# BLOCK6.net
KiCad netlist of a schematic drawn in Altium Designer
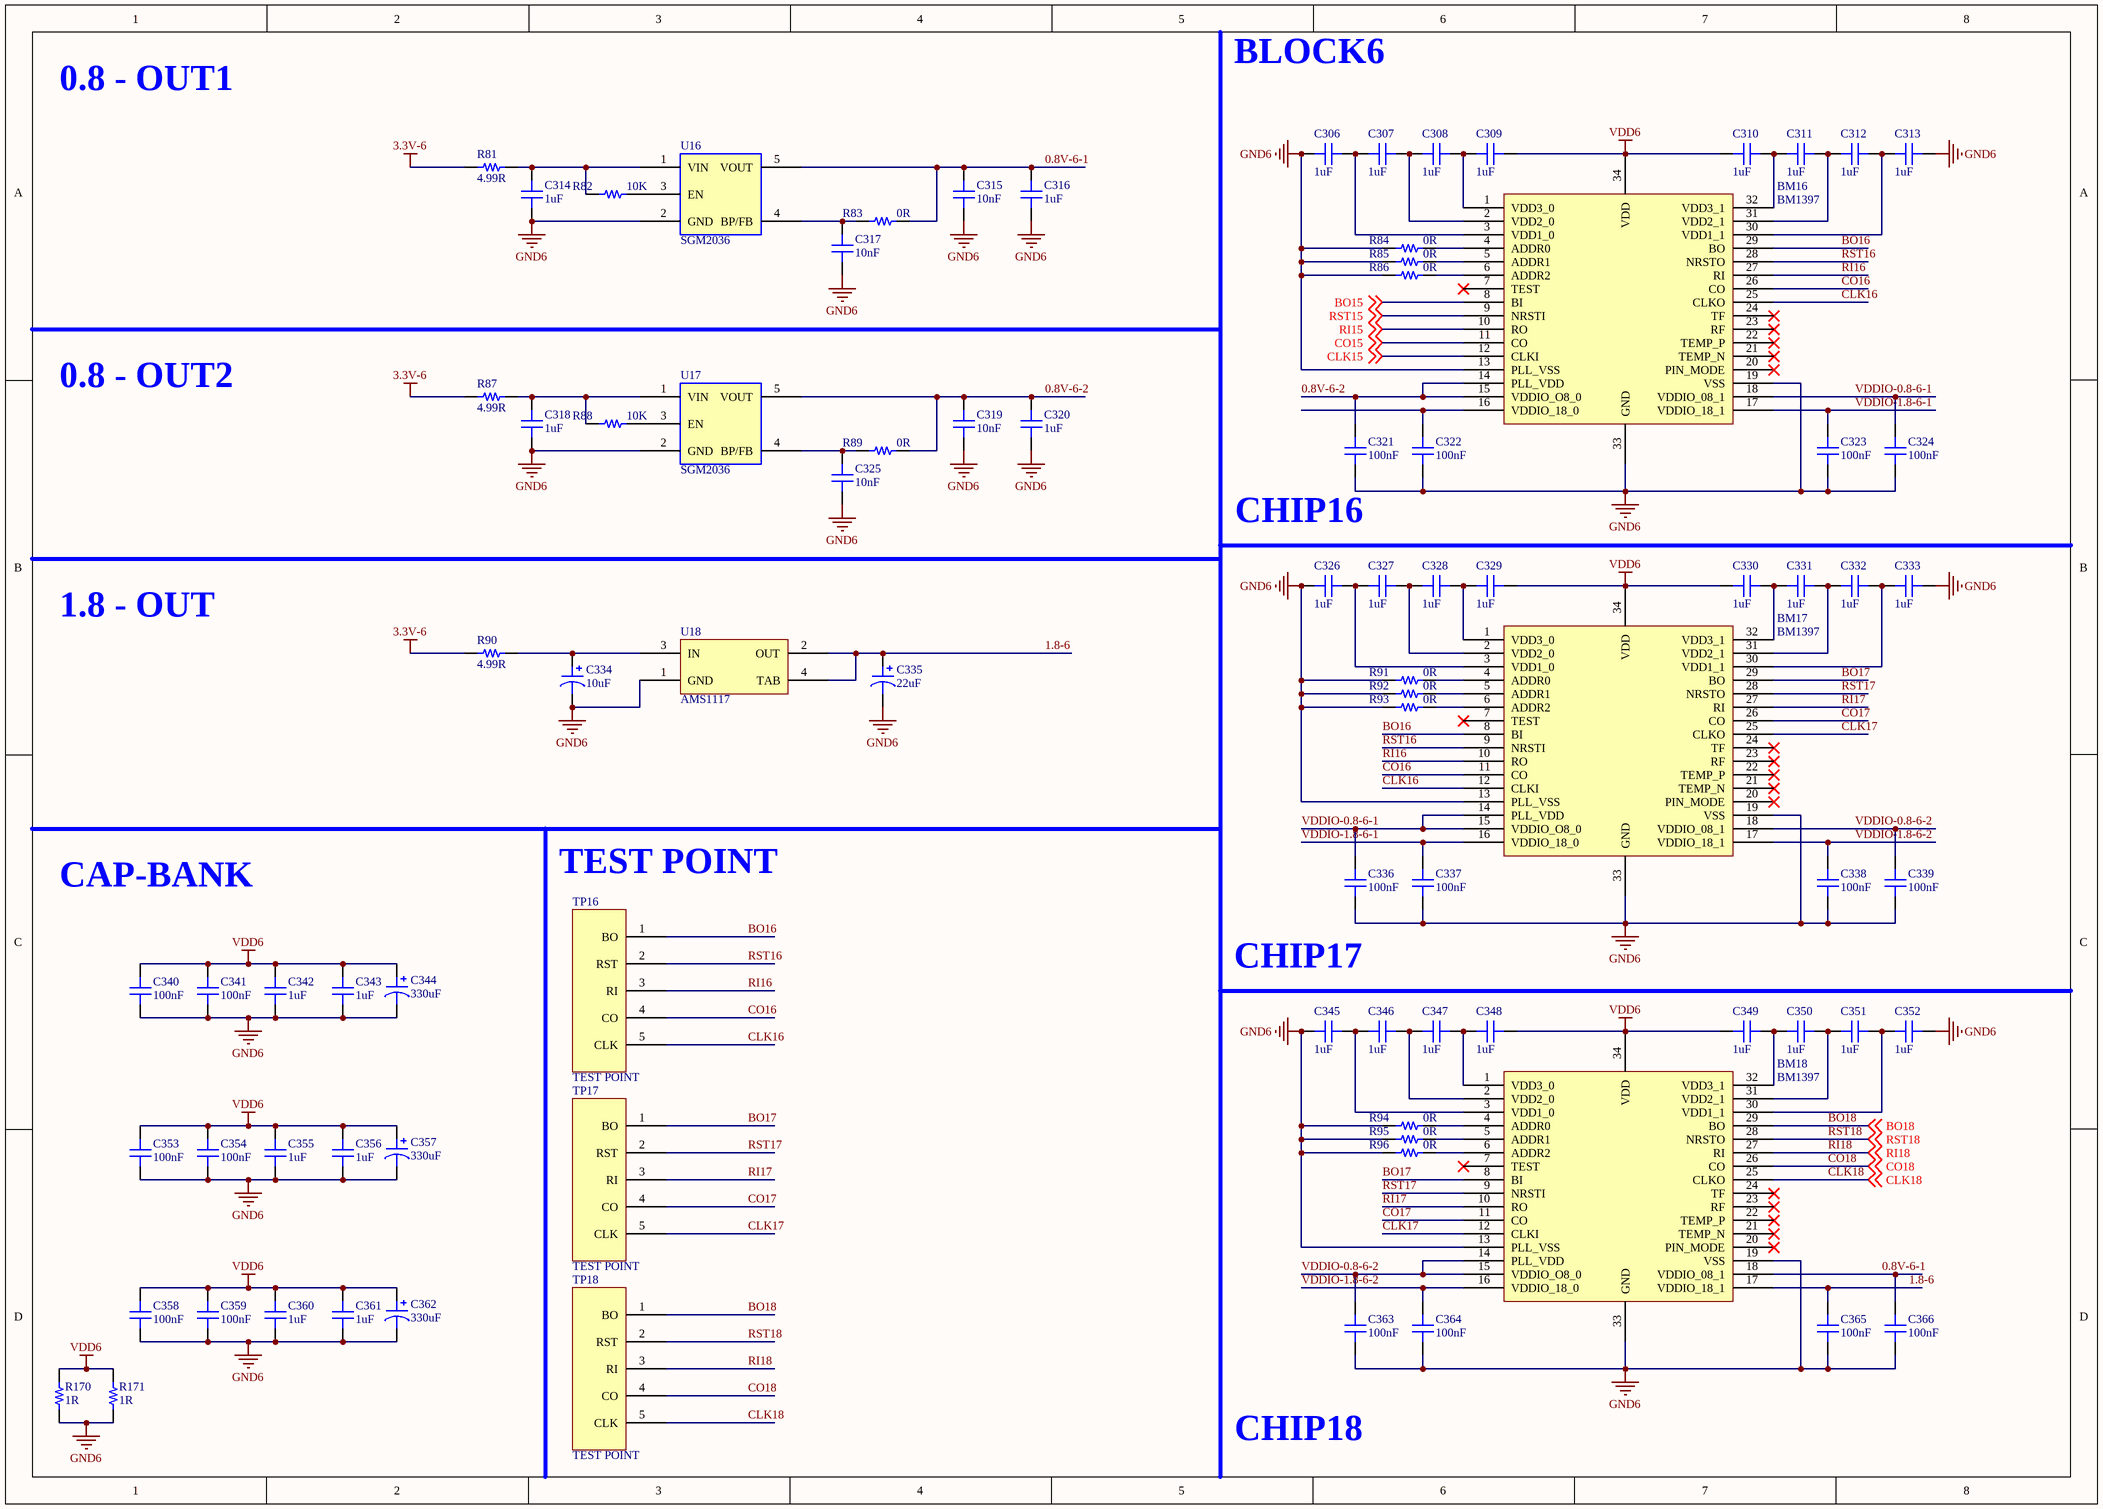
[diagram p0: BLOCK6.SchDoc]

(export (version "E")
  (design (tool "Eeschema 10.0.6"))
  (components
    (comp (ref "BM16") (value "BM1397") (footprint "BM1387") (libsource (lib "Miner_8TH") (part "BM1397_1")))
    (comp (ref "BM17") (value "BM1397") (footprint "BM1387") (libsource (lib "Miner_8TH") (part "BM1397_1")))
    (comp (ref "BM18") (value "BM1397") (footprint "BM1387") (libsource (lib "Miner_8TH") (part "BM1397_1")))
    (comp (ref "C306") (value "1uF") (footprint "CAP-SMD-0603") (libsource (lib "Miner_8TH") (part "CAP")))
    (comp (ref "C307") (value "1uF") (footprint "CAP-SMD-0603") (libsource (lib "Miner_8TH") (part "CAP")))
    (comp (ref "C308") (value "1uF") (footprint "CAP-SMD-0603") (libsource (lib "Miner_8TH") (part "CAP")))
    (comp (ref "C309") (value "1uF") (footprint "CAP-SMD-0603") (libsource (lib "Miner_8TH") (part "CAP")))
    (comp (ref "C310") (value "1uF") (footprint "CAP-SMD-0603") (libsource (lib "Miner_8TH") (part "CAP")))
    (comp (ref "C311") (value "1uF") (footprint "CAP-SMD-0603") (libsource (lib "Miner_8TH") (part "CAP")))
    (comp (ref "C312") (value "1uF") (footprint "CAP-SMD-0603") (libsource (lib "Miner_8TH") (part "CAP")))
    (comp (ref "C313") (value "1uF") (footprint "CAP-SMD-0603") (libsource (lib "Miner_8TH") (part "CAP")))
    (comp (ref "C314") (value "1uF") (footprint "CAP_SMD_0805") (libsource (lib "Miner_8TH") (part "CAP")))
    (comp (ref "C315") (value "10nF") (footprint "CAP_SMD_0805") (libsource (lib "Miner_8TH") (part "CAP")))
    (comp (ref "C316") (value "1uF") (footprint "CAP_SMD_0805") (libsource (lib "Miner_8TH") (part "CAP")))
    (comp (ref "C317") (value "10nF") (footprint "CAP_SMD_0805") (libsource (lib "Miner_8TH") (part "CAP")))
    (comp (ref "C318") (value "1uF") (footprint "CAP_SMD_0805") (libsource (lib "Miner_8TH") (part "CAP")))
    (comp (ref "C319") (value "10nF") (footprint "CAP_SMD_0805") (libsource (lib "Miner_8TH") (part "CAP")))
    (comp (ref "C320") (value "1uF") (footprint "CAP_SMD_0805") (libsource (lib "Miner_8TH") (part "CAP")))
    (comp (ref "C321") (value "100nF") (footprint "CAP_SMD_0805") (libsource (lib "Miner_8TH") (part "CAP")))
    (comp (ref "C322") (value "100nF") (footprint "CAP_SMD_0805") (libsource (lib "Miner_8TH") (part "CAP")))
    (comp (ref "C323") (value "100nF") (footprint "CAP_SMD_0805") (libsource (lib "Miner_8TH") (part "CAP")))
    (comp (ref "C324") (value "100nF") (footprint "CAP_SMD_0805") (libsource (lib "Miner_8TH") (part "CAP")))
    (comp (ref "C325") (value "10nF") (footprint "CAP_SMD_0805") (libsource (lib "Miner_8TH") (part "CAP")))
    (comp (ref "C326") (value "1uF") (footprint "CAP-SMD-0603") (libsource (lib "Miner_8TH") (part "CAP")))
    (comp (ref "C327") (value "1uF") (footprint "CAP-SMD-0603") (libsource (lib "Miner_8TH") (part "CAP")))
    (comp (ref "C328") (value "1uF") (footprint "CAP-SMD-0603") (libsource (lib "Miner_8TH") (part "CAP")))
    (comp (ref "C329") (value "1uF") (footprint "CAP-SMD-0603") (libsource (lib "Miner_8TH") (part "CAP")))
    (comp (ref "C330") (value "1uF") (footprint "CAP-SMD-0603") (libsource (lib "Miner_8TH") (part "CAP")))
    (comp (ref "C331") (value "1uF") (footprint "CAP-SMD-0603") (libsource (lib "Miner_8TH") (part "CAP")))
    (comp (ref "C332") (value "1uF") (footprint "CAP-SMD-0603") (libsource (lib "Miner_8TH") (part "CAP")))
    (comp (ref "C333") (value "1uF") (footprint "CAP-SMD-0603") (libsource (lib "Miner_8TH") (part "CAP")))
    (comp (ref "C334")
      (value "10uF")
      (footprint "CAP-TAN-CASE-A")
      (libsource (lib "Miner_8TH") (part "POLARIZED CAP"))
    )
    (comp (ref "C335")
      (value "22uF")
      (footprint "CAP-TAN-CASE-A")
      (libsource (lib "Miner_8TH") (part "POLARIZED CAP"))
    )
    (comp (ref "C336") (value "100nF") (footprint "CAP_SMD_0805") (libsource (lib "Miner_8TH") (part "CAP")))
    (comp (ref "C337") (value "100nF") (footprint "CAP_SMD_0805") (libsource (lib "Miner_8TH") (part "CAP")))
    (comp (ref "C338") (value "100nF") (footprint "CAP_SMD_0805") (libsource (lib "Miner_8TH") (part "CAP")))
    (comp (ref "C339") (value "100nF") (footprint "CAP_SMD_0805") (libsource (lib "Miner_8TH") (part "CAP")))
    (comp (ref "C340") (value "100nF") (footprint "CAP_SMD_0805") (libsource (lib "Miner_8TH") (part "CAP")))
    (comp (ref "C341") (value "100nF") (footprint "CAP_SMD_0805") (libsource (lib "Miner_8TH") (part "CAP")))
    (comp (ref "C342") (value "1uF") (footprint "CAP_SMD_0805") (libsource (lib "Miner_8TH") (part "CAP")))
    (comp (ref "C343") (value "1uF") (footprint "CAP_SMD_0805") (libsource (lib "Miner_8TH") (part "CAP")))
    (comp (ref "C344")
      (value "330uF")
      (footprint "CAP-TAN-CASE-E")
      (libsource (lib "Miner_8TH") (part "POLARIZED CAP"))
    )
    (comp (ref "C345") (value "1uF") (footprint "CAP-SMD-0603") (libsource (lib "Miner_8TH") (part "CAP")))
    (comp (ref "C346") (value "1uF") (footprint "CAP-SMD-0603") (libsource (lib "Miner_8TH") (part "CAP")))
    (comp (ref "C347") (value "1uF") (footprint "CAP-SMD-0603") (libsource (lib "Miner_8TH") (part "CAP")))
    (comp (ref "C348") (value "1uF") (footprint "CAP-SMD-0603") (libsource (lib "Miner_8TH") (part "CAP")))
    (comp (ref "C349") (value "1uF") (footprint "CAP-SMD-0603") (libsource (lib "Miner_8TH") (part "CAP")))
    (comp (ref "C350") (value "1uF") (footprint "CAP-SMD-0603") (libsource (lib "Miner_8TH") (part "CAP")))
    (comp (ref "C351") (value "1uF") (footprint "CAP-SMD-0603") (libsource (lib "Miner_8TH") (part "CAP")))
    (comp (ref "C352") (value "1uF") (footprint "CAP-SMD-0603") (libsource (lib "Miner_8TH") (part "CAP")))
    (comp (ref "C353") (value "100nF") (footprint "CAP_SMD_0805") (libsource (lib "Miner_8TH") (part "CAP")))
    (comp (ref "C354") (value "100nF") (footprint "CAP_SMD_0805") (libsource (lib "Miner_8TH") (part "CAP")))
    (comp (ref "C355") (value "1uF") (footprint "CAP_SMD_0805") (libsource (lib "Miner_8TH") (part "CAP")))
    (comp (ref "C356") (value "1uF") (footprint "CAP_SMD_0805") (libsource (lib "Miner_8TH") (part "CAP")))
    (comp (ref "C357")
      (value "330uF")
      (footprint "CAP-TAN-CASE-E")
      (libsource (lib "Miner_8TH") (part "POLARIZED CAP"))
    )
    (comp (ref "C358") (value "100nF") (footprint "CAP_SMD_0805") (libsource (lib "Miner_8TH") (part "CAP")))
    (comp (ref "C359") (value "100nF") (footprint "CAP_SMD_0805") (libsource (lib "Miner_8TH") (part "CAP")))
    (comp (ref "C360") (value "1uF") (footprint "CAP_SMD_0805") (libsource (lib "Miner_8TH") (part "CAP")))
    (comp (ref "C361") (value "1uF") (footprint "CAP_SMD_0805") (libsource (lib "Miner_8TH") (part "CAP")))
    (comp (ref "C362")
      (value "330uF")
      (footprint "CAP-TAN-CASE-E")
      (libsource (lib "Miner_8TH") (part "POLARIZED CAP"))
    )
    (comp (ref "C363") (value "100nF") (footprint "CAP_SMD_0805") (libsource (lib "Miner_8TH") (part "CAP")))
    (comp (ref "C364") (value "100nF") (footprint "CAP_SMD_0805") (libsource (lib "Miner_8TH") (part "CAP")))
    (comp (ref "C365") (value "100nF") (footprint "CAP_SMD_0805") (libsource (lib "Miner_8TH") (part "CAP")))
    (comp (ref "C366") (value "100nF") (footprint "CAP_SMD_0805") (libsource (lib "Miner_8TH") (part "CAP")))
    (comp (ref "R81") (value "4.99R") (footprint "RES-SMD-1206") (libsource (lib "Miner_8TH") (part "RES")))
    (comp (ref "R82") (value "10K") (footprint "RES-SMD-0402") (libsource (lib "Miner_8TH") (part "RES")))
    (comp (ref "R83") (value "0R") (footprint "RES-SMD-0402") (libsource (lib "Miner_8TH") (part "RES")))
    (comp (ref "R84") (value "0R") (footprint "RES-SMD-0402") (libsource (lib "Miner_8TH") (part "RES")))
    (comp (ref "R85") (value "0R") (footprint "RES-SMD-0402") (libsource (lib "Miner_8TH") (part "RES")))
    (comp (ref "R86") (value "0R") (footprint "RES-SMD-0402") (libsource (lib "Miner_8TH") (part "RES")))
    (comp (ref "R87") (value "4.99R") (footprint "RES-SMD-1206") (libsource (lib "Miner_8TH") (part "RES")))
    (comp (ref "R88") (value "10K") (footprint "RES-SMD-0402") (libsource (lib "Miner_8TH") (part "RES")))
    (comp (ref "R89") (value "0R") (footprint "RES-SMD-0402") (libsource (lib "Miner_8TH") (part "RES")))
    (comp (ref "R90") (value "4.99R") (footprint "RES-SMD-1206") (libsource (lib "Miner_8TH") (part "RES")))
    (comp (ref "R91") (value "0R") (footprint "RES-SMD-0402") (libsource (lib "Miner_8TH") (part "RES")))
    (comp (ref "R92") (value "0R") (footprint "RES-SMD-0402") (libsource (lib "Miner_8TH") (part "RES")))
    (comp (ref "R93") (value "0R") (footprint "RES-SMD-0402") (libsource (lib "Miner_8TH") (part "RES")))
    (comp (ref "R94") (value "0R") (footprint "RES-SMD-0402") (libsource (lib "Miner_8TH") (part "RES")))
    (comp (ref "R95") (value "0R") (footprint "RES-SMD-0402") (libsource (lib "Miner_8TH") (part "RES")))
    (comp (ref "R96") (value "0R") (footprint "RES-SMD-0402") (libsource (lib "Miner_8TH") (part "RES")))
    (comp (ref "R170") (value "1R") (footprint "RES-SMD-1210") (libsource (lib "Miner_8TH") (part "RES")))
    (comp (ref "R171") (value "1R") (footprint "RES-SMD-1210") (libsource (lib "Miner_8TH") (part "RES")))
    (comp (ref "TP16")
      (value "TEST POINT")
      (footprint "TEST_POINT")
      (libsource (lib "Miner_8TH") (part "TEST POINT"))
    )
    (comp (ref "TP17")
      (value "TEST POINT")
      (footprint "TEST_POINT")
      (libsource (lib "Miner_8TH") (part "TEST POINT"))
    )
    (comp (ref "TP18")
      (value "TEST POINT")
      (footprint "TEST_POINT")
      (libsource (lib "Miner_8TH") (part "TEST POINT"))
    )
    (comp (ref "U16")
      (value "SGM2036")
      (footprint "SOT23-5PIN")
      (libsource (lib "Miner_8TH") (part "SGM2036"))
    )
    (comp (ref "U17")
      (value "SGM2036")
      (footprint "SOT23-5PIN")
      (libsource (lib "Miner_8TH") (part "SGM2036"))
    )
    (comp (ref "U18") (value "AMS1117") (footprint "AMS1117") (libsource (lib "Miner_8TH") (part "AMS1117")))
  )
  (nets
    (net (code "1") (name "/0.8V-6-1") (class "Default")
      (node (ref "BM18") (pin "18") (pinfunction "VDDIO_08_1_18") (pintype "passive"))
      (node (ref "C315") (pin "2") (pinfunction "2_2") (pintype "passive"))
      (node (ref "C316") (pin "2") (pinfunction "2_2") (pintype "passive"))
      (node (ref "C366") (pin "2") (pinfunction "2_2") (pintype "passive"))
      (node (ref "R83") (pin "2") (pinfunction "2_2") (pintype "passive"))
      (node (ref "U16") (pin "5") (pinfunction "VOUT_5") (pintype "passive"))
    )
    (net (code "2") (name "/0.8V-6-2") (class "Default")
      (node (ref "BM16") (pin "14") (pinfunction "PLL_VDD_14") (pintype "passive"))
      (node (ref "BM16") (pin "15") (pinfunction "VDDIO_O8_0_15") (pintype "passive"))
      (node (ref "C319") (pin "2") (pinfunction "2_2") (pintype "passive"))
      (node (ref "C320") (pin "2") (pinfunction "2_2") (pintype "passive"))
      (node (ref "C321") (pin "2") (pinfunction "2_2") (pintype "passive"))
      (node (ref "R89") (pin "2") (pinfunction "2_2") (pintype "passive"))
      (node (ref "U17") (pin "5") (pinfunction "VOUT_5") (pintype "passive"))
    )
    (net (code "3") (name "/1.8-6") (class "Default")
      (node (ref "BM18") (pin "17") (pinfunction "VDDIO_18_1_17") (pintype "passive"))
      (node (ref "C335") (pin "1") (pinfunction "1_1") (pintype "passive"))
      (node (ref "C365") (pin "2") (pinfunction "2_2") (pintype "passive"))
      (node (ref "U18") (pin "2") (pinfunction "OUT_2") (pintype "passive"))
      (node (ref "U18") (pin "4") (pinfunction "TAB_4") (pintype "passive"))
    )
    (net (code "4") (name "/BO16") (class "Default")
      (node (ref "BM16") (pin "29") (pinfunction "BO_29") (pintype "passive"))
      (node (ref "BM17") (pin "8") (pinfunction "BI_8") (pintype "passive"))
      (node (ref "TP16") (pin "1") (pinfunction "BO_1") (pintype "passive"))
    )
    (net (code "5") (name "/BO17") (class "Default")
      (node (ref "BM17") (pin "29") (pinfunction "BO_29") (pintype "passive"))
      (node (ref "BM18") (pin "8") (pinfunction "BI_8") (pintype "passive"))
      (node (ref "TP17") (pin "1") (pinfunction "BO_1") (pintype "passive"))
    )
    (net (code "6") (name "/CLK16") (class "Default")
      (node (ref "BM16") (pin "25") (pinfunction "CLKO_25") (pintype "passive"))
      (node (ref "BM17") (pin "12") (pinfunction "CLKI_12") (pintype "passive"))
      (node (ref "TP16") (pin "5") (pinfunction "CLK_5") (pintype "passive"))
    )
    (net (code "7") (name "/CLK17") (class "Default")
      (node (ref "BM17") (pin "25") (pinfunction "CLKO_25") (pintype "passive"))
      (node (ref "BM18") (pin "12") (pinfunction "CLKI_12") (pintype "passive"))
      (node (ref "TP17") (pin "5") (pinfunction "CLK_5") (pintype "passive"))
    )
    (net (code "8") (name "/CO16") (class "Default")
      (node (ref "BM16") (pin "26") (pinfunction "CO_26") (pintype "passive"))
      (node (ref "BM17") (pin "11") (pinfunction "CO_11") (pintype "passive"))
      (node (ref "TP16") (pin "4") (pinfunction "CO_4") (pintype "passive"))
    )
    (net (code "9") (name "/CO17") (class "Default")
      (node (ref "BM17") (pin "26") (pinfunction "CO_26") (pintype "passive"))
      (node (ref "BM18") (pin "11") (pinfunction "CO_11") (pintype "passive"))
      (node (ref "TP17") (pin "4") (pinfunction "CO_4") (pintype "passive"))
    )
    (net (code "10") (name "/RI16") (class "Default")
      (node (ref "BM16") (pin "27") (pinfunction "RI_27") (pintype "passive"))
      (node (ref "BM17") (pin "10") (pinfunction "RO_10") (pintype "passive"))
      (node (ref "TP16") (pin "3") (pinfunction "RI_3") (pintype "passive"))
    )
    (net (code "11") (name "/RI17") (class "Default")
      (node (ref "BM17") (pin "27") (pinfunction "RI_27") (pintype "passive"))
      (node (ref "BM18") (pin "10") (pinfunction "RO_10") (pintype "passive"))
      (node (ref "TP17") (pin "3") (pinfunction "RI_3") (pintype "passive"))
    )
    (net (code "12") (name "/RST16") (class "Default")
      (node (ref "BM16") (pin "28") (pinfunction "NRSTO_28") (pintype "passive"))
      (node (ref "BM17") (pin "9") (pinfunction "NRSTI_9") (pintype "passive"))
      (node (ref "TP16") (pin "2") (pinfunction "RST_2") (pintype "passive"))
    )
    (net (code "13") (name "/RST17") (class "Default")
      (node (ref "BM17") (pin "28") (pinfunction "NRSTO_28") (pintype "passive"))
      (node (ref "BM18") (pin "9") (pinfunction "NRSTI_9") (pintype "passive"))
      (node (ref "TP17") (pin "2") (pinfunction "RST_2") (pintype "passive"))
    )
    (net (code "14") (name "/VDDIO-0.8-6-1") (class "Default")
      (node (ref "BM16") (pin "18") (pinfunction "VDDIO_08_1_18") (pintype "passive"))
      (node (ref "BM17") (pin "14") (pinfunction "PLL_VDD_14") (pintype "passive"))
      (node (ref "BM17") (pin "15") (pinfunction "VDDIO_O8_0_15") (pintype "passive"))
      (node (ref "C324") (pin "2") (pinfunction "2_2") (pintype "passive"))
      (node (ref "C336") (pin "2") (pinfunction "2_2") (pintype "passive"))
    )
    (net (code "15") (name "/VDDIO-0.8-6-2") (class "Default")
      (node (ref "BM17") (pin "18") (pinfunction "VDDIO_08_1_18") (pintype "passive"))
      (node (ref "BM18") (pin "14") (pinfunction "PLL_VDD_14") (pintype "passive"))
      (node (ref "BM18") (pin "15") (pinfunction "VDDIO_O8_0_15") (pintype "passive"))
      (node (ref "C339") (pin "2") (pinfunction "2_2") (pintype "passive"))
      (node (ref "C363") (pin "2") (pinfunction "2_2") (pintype "passive"))
    )
    (net (code "16") (name "/VDDIO-1.8-6-1") (class "Default")
      (node (ref "BM16") (pin "17") (pinfunction "VDDIO_18_1_17") (pintype "passive"))
      (node (ref "BM17") (pin "16") (pinfunction "VDDIO_18_0_16") (pintype "passive"))
      (node (ref "C323") (pin "2") (pinfunction "2_2") (pintype "passive"))
      (node (ref "C337") (pin "2") (pinfunction "2_2") (pintype "passive"))
    )
    (net (code "17") (name "/VDDIO-1.8-6-2") (class "Default")
      (node (ref "BM17") (pin "17") (pinfunction "VDDIO_18_1_17") (pintype "passive"))
      (node (ref "BM18") (pin "16") (pinfunction "VDDIO_18_0_16") (pintype "passive"))
      (node (ref "C338") (pin "2") (pinfunction "2_2") (pintype "passive"))
      (node (ref "C364") (pin "2") (pinfunction "2_2") (pintype "passive"))
    )
    (net (code "18") (name "3.3V-6") (class "Default")
      (node (ref "R81") (pin "1") (pinfunction "1_1") (pintype "passive"))
      (node (ref "R87") (pin "1") (pinfunction "1_1") (pintype "passive"))
      (node (ref "R90") (pin "1") (pinfunction "1_1") (pintype "passive"))
    )
    (net (code "19") (name "BO15") (class "Default")
      (node (ref "BM16") (pin "8") (pinfunction "BI_8") (pintype "passive"))
    )
    (net (code "20") (name "BO18") (class "Default")
      (node (ref "BM18") (pin "29") (pinfunction "BO_29") (pintype "passive"))
      (node (ref "TP18") (pin "1") (pinfunction "BO_1") (pintype "passive"))
    )
    (net (code "21") (name "CLK15") (class "Default")
      (node (ref "BM16") (pin "12") (pinfunction "CLKI_12") (pintype "passive"))
    )
    (net (code "22") (name "CLK18") (class "Default")
      (node (ref "BM18") (pin "25") (pinfunction "CLKO_25") (pintype "passive"))
      (node (ref "TP18") (pin "5") (pinfunction "CLK_5") (pintype "passive"))
    )
    (net (code "23") (name "CO15") (class "Default")
      (node (ref "BM16") (pin "11") (pinfunction "CO_11") (pintype "passive"))
    )
    (net (code "24") (name "CO18") (class "Default")
      (node (ref "BM18") (pin "26") (pinfunction "CO_26") (pintype "passive"))
      (node (ref "TP18") (pin "4") (pinfunction "CO_4") (pintype "passive"))
    )
    (net (code "25") (name "GND6") (class "Default")
      (node (ref "BM16") (pin "13") (pinfunction "PLL_VSS_13") (pintype "passive"))
      (node (ref "BM16") (pin "19") (pinfunction "VSS_19") (pintype "passive"))
      (node (ref "BM16") (pin "33") (pinfunction "GND_33") (pintype "passive"))
      (node (ref "BM17") (pin "13") (pinfunction "PLL_VSS_13") (pintype "passive"))
      (node (ref "BM17") (pin "19") (pinfunction "VSS_19") (pintype "passive"))
      (node (ref "BM17") (pin "33") (pinfunction "GND_33") (pintype "passive"))
      (node (ref "BM18") (pin "13") (pinfunction "PLL_VSS_13") (pintype "passive"))
      (node (ref "BM18") (pin "19") (pinfunction "VSS_19") (pintype "passive"))
      (node (ref "BM18") (pin "33") (pinfunction "GND_33") (pintype "passive"))
      (node (ref "C306") (pin "1") (pinfunction "1_1") (pintype "passive"))
      (node (ref "C313") (pin "2") (pinfunction "2_2") (pintype "passive"))
      (node (ref "C314") (pin "1") (pinfunction "1_1") (pintype "passive"))
      (node (ref "C315") (pin "1") (pinfunction "1_1") (pintype "passive"))
      (node (ref "C316") (pin "1") (pinfunction "1_1") (pintype "passive"))
      (node (ref "C317") (pin "1") (pinfunction "1_1") (pintype "passive"))
      (node (ref "C318") (pin "1") (pinfunction "1_1") (pintype "passive"))
      (node (ref "C319") (pin "1") (pinfunction "1_1") (pintype "passive"))
      (node (ref "C320") (pin "1") (pinfunction "1_1") (pintype "passive"))
      (node (ref "C321") (pin "1") (pinfunction "1_1") (pintype "passive"))
      (node (ref "C322") (pin "1") (pinfunction "1_1") (pintype "passive"))
      (node (ref "C323") (pin "1") (pinfunction "1_1") (pintype "passive"))
      (node (ref "C324") (pin "1") (pinfunction "1_1") (pintype "passive"))
      (node (ref "C325") (pin "1") (pinfunction "1_1") (pintype "passive"))
      (node (ref "C326") (pin "1") (pinfunction "1_1") (pintype "passive"))
      (node (ref "C333") (pin "2") (pinfunction "2_2") (pintype "passive"))
      (node (ref "C334") (pin "2") (pinfunction "2_2") (pintype "passive"))
      (node (ref "C335") (pin "2") (pinfunction "2_2") (pintype "passive"))
      (node (ref "C336") (pin "1") (pinfunction "1_1") (pintype "passive"))
      (node (ref "C337") (pin "1") (pinfunction "1_1") (pintype "passive"))
      (node (ref "C338") (pin "1") (pinfunction "1_1") (pintype "passive"))
      (node (ref "C339") (pin "1") (pinfunction "1_1") (pintype "passive"))
      (node (ref "C340") (pin "1") (pinfunction "1_1") (pintype "passive"))
      (node (ref "C341") (pin "1") (pinfunction "1_1") (pintype "passive"))
      (node (ref "C342") (pin "1") (pinfunction "1_1") (pintype "passive"))
      (node (ref "C343") (pin "1") (pinfunction "1_1") (pintype "passive"))
      (node (ref "C344") (pin "2") (pinfunction "2_2") (pintype "passive"))
      (node (ref "C345") (pin "1") (pinfunction "1_1") (pintype "passive"))
      (node (ref "C352") (pin "2") (pinfunction "2_2") (pintype "passive"))
      (node (ref "C353") (pin "1") (pinfunction "1_1") (pintype "passive"))
      (node (ref "C354") (pin "1") (pinfunction "1_1") (pintype "passive"))
      (node (ref "C355") (pin "1") (pinfunction "1_1") (pintype "passive"))
      (node (ref "C356") (pin "1") (pinfunction "1_1") (pintype "passive"))
      (node (ref "C357") (pin "2") (pinfunction "2_2") (pintype "passive"))
      (node (ref "C358") (pin "1") (pinfunction "1_1") (pintype "passive"))
      (node (ref "C359") (pin "1") (pinfunction "1_1") (pintype "passive"))
      (node (ref "C360") (pin "1") (pinfunction "1_1") (pintype "passive"))
      (node (ref "C361") (pin "1") (pinfunction "1_1") (pintype "passive"))
      (node (ref "C362") (pin "2") (pinfunction "2_2") (pintype "passive"))
      (node (ref "C363") (pin "1") (pinfunction "1_1") (pintype "passive"))
      (node (ref "C364") (pin "1") (pinfunction "1_1") (pintype "passive"))
      (node (ref "C365") (pin "1") (pinfunction "1_1") (pintype "passive"))
      (node (ref "C366") (pin "1") (pinfunction "1_1") (pintype "passive"))
      (node (ref "R170") (pin "1") (pinfunction "1_1") (pintype "passive"))
      (node (ref "R171") (pin "1") (pinfunction "1_1") (pintype "passive"))
      (node (ref "R84") (pin "1") (pinfunction "1_1") (pintype "passive"))
      (node (ref "R85") (pin "1") (pinfunction "1_1") (pintype "passive"))
      (node (ref "R86") (pin "1") (pinfunction "1_1") (pintype "passive"))
      (node (ref "R91") (pin "1") (pinfunction "1_1") (pintype "passive"))
      (node (ref "R92") (pin "1") (pinfunction "1_1") (pintype "passive"))
      (node (ref "R93") (pin "1") (pinfunction "1_1") (pintype "passive"))
      (node (ref "R94") (pin "1") (pinfunction "1_1") (pintype "passive"))
      (node (ref "R95") (pin "1") (pinfunction "1_1") (pintype "passive"))
      (node (ref "R96") (pin "1") (pinfunction "1_1") (pintype "passive"))
      (node (ref "U16") (pin "2") (pinfunction "GND_2") (pintype "passive"))
      (node (ref "U17") (pin "2") (pinfunction "GND_2") (pintype "passive"))
      (node (ref "U18") (pin "1") (pinfunction "GND_1") (pintype "passive"))
    )
    (net (code "26") (name "Net-(BM16-ADDR0)") (class "Default")
      (node (ref "BM16") (pin "4") (pinfunction "ADDR0_4") (pintype "passive"))
      (node (ref "R84") (pin "2") (pinfunction "2_2") (pintype "passive"))
    )
    (net (code "27") (name "Net-(BM16-ADDR1)") (class "Default")
      (node (ref "BM16") (pin "5") (pinfunction "ADDR1_5") (pintype "passive"))
      (node (ref "R85") (pin "2") (pinfunction "2_2") (pintype "passive"))
    )
    (net (code "28") (name "Net-(BM16-ADDR2)") (class "Default")
      (node (ref "BM16") (pin "6") (pinfunction "ADDR2_6") (pintype "passive"))
      (node (ref "R86") (pin "2") (pinfunction "2_2") (pintype "passive"))
    )
    (net (code "29") (name "Net-(BM16-VDD1_0)") (class "Default")
      (node (ref "BM16") (pin "3") (pinfunction "VDD1_0_3") (pintype "passive"))
      (node (ref "C306") (pin "2") (pinfunction "2_2") (pintype "passive"))
      (node (ref "C307") (pin "1") (pinfunction "1_1") (pintype "passive"))
    )
    (net (code "30") (name "Net-(BM16-VDD1_1)") (class "Default")
      (node (ref "BM16") (pin "30") (pinfunction "VDD1_1_30") (pintype "passive"))
      (node (ref "C312") (pin "2") (pinfunction "2_2") (pintype "passive"))
      (node (ref "C313") (pin "1") (pinfunction "1_1") (pintype "passive"))
    )
    (net (code "31") (name "Net-(BM16-VDD2_0)") (class "Default")
      (node (ref "BM16") (pin "2") (pinfunction "VDD2_0_2") (pintype "passive"))
      (node (ref "C307") (pin "2") (pinfunction "2_2") (pintype "passive"))
      (node (ref "C308") (pin "1") (pinfunction "1_1") (pintype "passive"))
    )
    (net (code "32") (name "Net-(BM16-VDD2_1)") (class "Default")
      (node (ref "BM16") (pin "31") (pinfunction "VDD2_1_31") (pintype "passive"))
      (node (ref "C311") (pin "2") (pinfunction "2_2") (pintype "passive"))
      (node (ref "C312") (pin "1") (pinfunction "1_1") (pintype "passive"))
    )
    (net (code "33") (name "Net-(BM16-VDD3_0)") (class "Default")
      (node (ref "BM16") (pin "1") (pinfunction "VDD3_0_1") (pintype "passive"))
      (node (ref "C308") (pin "2") (pinfunction "2_2") (pintype "passive"))
      (node (ref "C309") (pin "1") (pinfunction "1_1") (pintype "passive"))
    )
    (net (code "34") (name "Net-(BM16-VDD3_1)") (class "Default")
      (node (ref "BM16") (pin "32") (pinfunction "VDD3_1_32") (pintype "passive"))
      (node (ref "C310") (pin "2") (pinfunction "2_2") (pintype "passive"))
      (node (ref "C311") (pin "1") (pinfunction "1_1") (pintype "passive"))
    )
    (net (code "35") (name "Net-(BM16-VDDIO_18_0)") (class "Default")
      (node (ref "BM16") (pin "16") (pinfunction "VDDIO_18_0_16") (pintype "passive"))
      (node (ref "C322") (pin "2") (pinfunction "2_2") (pintype "passive"))
    )
    (net (code "36") (name "Net-(BM17-ADDR0)") (class "Default")
      (node (ref "BM17") (pin "4") (pinfunction "ADDR0_4") (pintype "passive"))
      (node (ref "R91") (pin "2") (pinfunction "2_2") (pintype "passive"))
    )
    (net (code "37") (name "Net-(BM17-ADDR1)") (class "Default")
      (node (ref "BM17") (pin "5") (pinfunction "ADDR1_5") (pintype "passive"))
      (node (ref "R92") (pin "2") (pinfunction "2_2") (pintype "passive"))
    )
    (net (code "38") (name "Net-(BM17-ADDR2)") (class "Default")
      (node (ref "BM17") (pin "6") (pinfunction "ADDR2_6") (pintype "passive"))
      (node (ref "R93") (pin "2") (pinfunction "2_2") (pintype "passive"))
    )
    (net (code "39") (name "Net-(BM17-VDD1_0)") (class "Default")
      (node (ref "BM17") (pin "3") (pinfunction "VDD1_0_3") (pintype "passive"))
      (node (ref "C326") (pin "2") (pinfunction "2_2") (pintype "passive"))
      (node (ref "C327") (pin "1") (pinfunction "1_1") (pintype "passive"))
    )
    (net (code "40") (name "Net-(BM17-VDD1_1)") (class "Default")
      (node (ref "BM17") (pin "30") (pinfunction "VDD1_1_30") (pintype "passive"))
      (node (ref "C332") (pin "2") (pinfunction "2_2") (pintype "passive"))
      (node (ref "C333") (pin "1") (pinfunction "1_1") (pintype "passive"))
    )
    (net (code "41") (name "Net-(BM17-VDD2_0)") (class "Default")
      (node (ref "BM17") (pin "2") (pinfunction "VDD2_0_2") (pintype "passive"))
      (node (ref "C327") (pin "2") (pinfunction "2_2") (pintype "passive"))
      (node (ref "C328") (pin "1") (pinfunction "1_1") (pintype "passive"))
    )
    (net (code "42") (name "Net-(BM17-VDD2_1)") (class "Default")
      (node (ref "BM17") (pin "31") (pinfunction "VDD2_1_31") (pintype "passive"))
      (node (ref "C331") (pin "2") (pinfunction "2_2") (pintype "passive"))
      (node (ref "C332") (pin "1") (pinfunction "1_1") (pintype "passive"))
    )
    (net (code "43") (name "Net-(BM17-VDD3_0)") (class "Default")
      (node (ref "BM17") (pin "1") (pinfunction "VDD3_0_1") (pintype "passive"))
      (node (ref "C328") (pin "2") (pinfunction "2_2") (pintype "passive"))
      (node (ref "C329") (pin "1") (pinfunction "1_1") (pintype "passive"))
    )
    (net (code "44") (name "Net-(BM17-VDD3_1)") (class "Default")
      (node (ref "BM17") (pin "32") (pinfunction "VDD3_1_32") (pintype "passive"))
      (node (ref "C330") (pin "2") (pinfunction "2_2") (pintype "passive"))
      (node (ref "C331") (pin "1") (pinfunction "1_1") (pintype "passive"))
    )
    (net (code "45") (name "Net-(BM18-ADDR0)") (class "Default")
      (node (ref "BM18") (pin "4") (pinfunction "ADDR0_4") (pintype "passive"))
      (node (ref "R94") (pin "2") (pinfunction "2_2") (pintype "passive"))
    )
    (net (code "46") (name "Net-(BM18-ADDR1)") (class "Default")
      (node (ref "BM18") (pin "5") (pinfunction "ADDR1_5") (pintype "passive"))
      (node (ref "R95") (pin "2") (pinfunction "2_2") (pintype "passive"))
    )
    (net (code "47") (name "Net-(BM18-ADDR2)") (class "Default")
      (node (ref "BM18") (pin "6") (pinfunction "ADDR2_6") (pintype "passive"))
      (node (ref "R96") (pin "2") (pinfunction "2_2") (pintype "passive"))
    )
    (net (code "48") (name "Net-(BM18-VDD1_0)") (class "Default")
      (node (ref "BM18") (pin "3") (pinfunction "VDD1_0_3") (pintype "passive"))
      (node (ref "C345") (pin "2") (pinfunction "2_2") (pintype "passive"))
      (node (ref "C346") (pin "1") (pinfunction "1_1") (pintype "passive"))
    )
    (net (code "49") (name "Net-(BM18-VDD1_1)") (class "Default")
      (node (ref "BM18") (pin "30") (pinfunction "VDD1_1_30") (pintype "passive"))
      (node (ref "C351") (pin "2") (pinfunction "2_2") (pintype "passive"))
      (node (ref "C352") (pin "1") (pinfunction "1_1") (pintype "passive"))
    )
    (net (code "50") (name "Net-(BM18-VDD2_0)") (class "Default")
      (node (ref "BM18") (pin "2") (pinfunction "VDD2_0_2") (pintype "passive"))
      (node (ref "C346") (pin "2") (pinfunction "2_2") (pintype "passive"))
      (node (ref "C347") (pin "1") (pinfunction "1_1") (pintype "passive"))
    )
    (net (code "51") (name "Net-(BM18-VDD2_1)") (class "Default")
      (node (ref "BM18") (pin "31") (pinfunction "VDD2_1_31") (pintype "passive"))
      (node (ref "C350") (pin "2") (pinfunction "2_2") (pintype "passive"))
      (node (ref "C351") (pin "1") (pinfunction "1_1") (pintype "passive"))
    )
    (net (code "52") (name "Net-(BM18-VDD3_0)") (class "Default")
      (node (ref "BM18") (pin "1") (pinfunction "VDD3_0_1") (pintype "passive"))
      (node (ref "C347") (pin "2") (pinfunction "2_2") (pintype "passive"))
      (node (ref "C348") (pin "1") (pinfunction "1_1") (pintype "passive"))
    )
    (net (code "53") (name "Net-(BM18-VDD3_1)") (class "Default")
      (node (ref "BM18") (pin "32") (pinfunction "VDD3_1_32") (pintype "passive"))
      (node (ref "C349") (pin "2") (pinfunction "2_2") (pintype "passive"))
      (node (ref "C350") (pin "1") (pinfunction "1_1") (pintype "passive"))
    )
    (net (code "54") (name "Net-(U16-BP{slash}FB)") (class "Default")
      (node (ref "C317") (pin "2") (pinfunction "2_2") (pintype "passive"))
      (node (ref "R83") (pin "1") (pinfunction "1_1") (pintype "passive"))
      (node (ref "U16") (pin "4") (pinfunction "BP/FB_4") (pintype "passive"))
    )
    (net (code "55") (name "Net-(U16-EN)") (class "Default")
      (node (ref "R82") (pin "2") (pinfunction "2_2") (pintype "passive"))
      (node (ref "U16") (pin "3") (pinfunction "EN_3") (pintype "passive"))
    )
    (net (code "56") (name "Net-(U16-VIN)") (class "Default")
      (node (ref "C314") (pin "2") (pinfunction "2_2") (pintype "passive"))
      (node (ref "R81") (pin "2") (pinfunction "2_2") (pintype "passive"))
      (node (ref "R82") (pin "1") (pinfunction "1_1") (pintype "passive"))
      (node (ref "U16") (pin "1") (pinfunction "VIN_1") (pintype "passive"))
    )
    (net (code "57") (name "Net-(U17-BP{slash}FB)") (class "Default")
      (node (ref "C325") (pin "2") (pinfunction "2_2") (pintype "passive"))
      (node (ref "R89") (pin "1") (pinfunction "1_1") (pintype "passive"))
      (node (ref "U17") (pin "4") (pinfunction "BP/FB_4") (pintype "passive"))
    )
    (net (code "58") (name "Net-(U17-EN)") (class "Default")
      (node (ref "R88") (pin "2") (pinfunction "2_2") (pintype "passive"))
      (node (ref "U17") (pin "3") (pinfunction "EN_3") (pintype "passive"))
    )
    (net (code "59") (name "Net-(U17-VIN)") (class "Default")
      (node (ref "C318") (pin "2") (pinfunction "2_2") (pintype "passive"))
      (node (ref "R87") (pin "2") (pinfunction "2_2") (pintype "passive"))
      (node (ref "R88") (pin "1") (pinfunction "1_1") (pintype "passive"))
      (node (ref "U17") (pin "1") (pinfunction "VIN_1") (pintype "passive"))
    )
    (net (code "60") (name "Net-(U18-IN)") (class "Default")
      (node (ref "C334") (pin "1") (pinfunction "1_1") (pintype "passive"))
      (node (ref "R90") (pin "2") (pinfunction "2_2") (pintype "passive"))
      (node (ref "U18") (pin "3") (pinfunction "IN_3") (pintype "passive"))
    )
    (net (code "61") (name "RI15") (class "Default")
      (node (ref "BM16") (pin "10") (pinfunction "RO_10") (pintype "passive"))
    )
    (net (code "62") (name "RI18") (class "Default")
      (node (ref "BM18") (pin "27") (pinfunction "RI_27") (pintype "passive"))
      (node (ref "TP18") (pin "3") (pinfunction "RI_3") (pintype "passive"))
    )
    (net (code "63") (name "RST15") (class "Default")
      (node (ref "BM16") (pin "9") (pinfunction "NRSTI_9") (pintype "passive"))
    )
    (net (code "64") (name "RST18") (class "Default")
      (node (ref "BM18") (pin "28") (pinfunction "NRSTO_28") (pintype "passive"))
      (node (ref "TP18") (pin "2") (pinfunction "RST_2") (pintype "passive"))
    )
    (net (code "65") (name "VDD6") (class "Default")
      (node (ref "BM16") (pin "34") (pinfunction "VDD_34") (pintype "passive"))
      (node (ref "BM17") (pin "34") (pinfunction "VDD_34") (pintype "passive"))
      (node (ref "BM18") (pin "34") (pinfunction "VDD_34") (pintype "passive"))
      (node (ref "C309") (pin "2") (pinfunction "2_2") (pintype "passive"))
      (node (ref "C310") (pin "1") (pinfunction "1_1") (pintype "passive"))
      (node (ref "C329") (pin "2") (pinfunction "2_2") (pintype "passive"))
      (node (ref "C330") (pin "1") (pinfunction "1_1") (pintype "passive"))
      (node (ref "C340") (pin "2") (pinfunction "2_2") (pintype "passive"))
      (node (ref "C341") (pin "2") (pinfunction "2_2") (pintype "passive"))
      (node (ref "C342") (pin "2") (pinfunction "2_2") (pintype "passive"))
      (node (ref "C343") (pin "2") (pinfunction "2_2") (pintype "passive"))
      (node (ref "C344") (pin "1") (pinfunction "1_1") (pintype "passive"))
      (node (ref "C348") (pin "2") (pinfunction "2_2") (pintype "passive"))
      (node (ref "C349") (pin "1") (pinfunction "1_1") (pintype "passive"))
      (node (ref "C353") (pin "2") (pinfunction "2_2") (pintype "passive"))
      (node (ref "C354") (pin "2") (pinfunction "2_2") (pintype "passive"))
      (node (ref "C355") (pin "2") (pinfunction "2_2") (pintype "passive"))
      (node (ref "C356") (pin "2") (pinfunction "2_2") (pintype "passive"))
      (node (ref "C357") (pin "1") (pinfunction "1_1") (pintype "passive"))
      (node (ref "C358") (pin "2") (pinfunction "2_2") (pintype "passive"))
      (node (ref "C359") (pin "2") (pinfunction "2_2") (pintype "passive"))
      (node (ref "C360") (pin "2") (pinfunction "2_2") (pintype "passive"))
      (node (ref "C361") (pin "2") (pinfunction "2_2") (pintype "passive"))
      (node (ref "C362") (pin "1") (pinfunction "1_1") (pintype "passive"))
      (node (ref "R170") (pin "2") (pinfunction "2_2") (pintype "passive"))
      (node (ref "R171") (pin "2") (pinfunction "2_2") (pintype "passive"))
    )
    (net (code "66") (name "unconnected-(BM16-PIN_MODE-Pad20)") (class "Default")
      (node (ref "BM16") (pin "20") (pinfunction "PIN_MODE_20") (pintype "passive+no_connect"))
    )
    (net (code "67") (name "unconnected-(BM16-RF-Pad23)") (class "Default")
      (node (ref "BM16") (pin "23") (pinfunction "RF_23") (pintype "passive+no_connect"))
    )
    (net (code "68") (name "unconnected-(BM16-TEMP_N-Pad21)") (class "Default")
      (node (ref "BM16") (pin "21") (pinfunction "TEMP_N_21") (pintype "passive+no_connect"))
    )
    (net (code "69") (name "unconnected-(BM16-TEMP_P-Pad22)") (class "Default")
      (node (ref "BM16") (pin "22") (pinfunction "TEMP_P_22") (pintype "passive+no_connect"))
    )
    (net (code "70") (name "unconnected-(BM16-TEST-Pad7)") (class "Default")
      (node (ref "BM16") (pin "7") (pinfunction "TEST_7") (pintype "passive+no_connect"))
    )
    (net (code "71") (name "unconnected-(BM16-TF-Pad24)") (class "Default")
      (node (ref "BM16") (pin "24") (pinfunction "TF_24") (pintype "passive+no_connect"))
    )
    (net (code "72") (name "unconnected-(BM17-PIN_MODE-Pad20)") (class "Default")
      (node (ref "BM17") (pin "20") (pinfunction "PIN_MODE_20") (pintype "passive+no_connect"))
    )
    (net (code "73") (name "unconnected-(BM17-RF-Pad23)") (class "Default")
      (node (ref "BM17") (pin "23") (pinfunction "RF_23") (pintype "passive+no_connect"))
    )
    (net (code "74") (name "unconnected-(BM17-TEMP_N-Pad21)") (class "Default")
      (node (ref "BM17") (pin "21") (pinfunction "TEMP_N_21") (pintype "passive+no_connect"))
    )
    (net (code "75") (name "unconnected-(BM17-TEMP_P-Pad22)") (class "Default")
      (node (ref "BM17") (pin "22") (pinfunction "TEMP_P_22") (pintype "passive+no_connect"))
    )
    (net (code "76") (name "unconnected-(BM17-TEST-Pad7)") (class "Default")
      (node (ref "BM17") (pin "7") (pinfunction "TEST_7") (pintype "passive+no_connect"))
    )
    (net (code "77") (name "unconnected-(BM17-TF-Pad24)") (class "Default")
      (node (ref "BM17") (pin "24") (pinfunction "TF_24") (pintype "passive+no_connect"))
    )
    (net (code "78") (name "unconnected-(BM18-PIN_MODE-Pad20)") (class "Default")
      (node (ref "BM18") (pin "20") (pinfunction "PIN_MODE_20") (pintype "passive+no_connect"))
    )
    (net (code "79") (name "unconnected-(BM18-RF-Pad23)") (class "Default")
      (node (ref "BM18") (pin "23") (pinfunction "RF_23") (pintype "passive+no_connect"))
    )
    (net (code "80") (name "unconnected-(BM18-TEMP_N-Pad21)") (class "Default")
      (node (ref "BM18") (pin "21") (pinfunction "TEMP_N_21") (pintype "passive+no_connect"))
    )
    (net (code "81") (name "unconnected-(BM18-TEMP_P-Pad22)") (class "Default")
      (node (ref "BM18") (pin "22") (pinfunction "TEMP_P_22") (pintype "passive+no_connect"))
    )
    (net (code "82") (name "unconnected-(BM18-TEST-Pad7)") (class "Default")
      (node (ref "BM18") (pin "7") (pinfunction "TEST_7") (pintype "passive+no_connect"))
    )
    (net (code "83") (name "unconnected-(BM18-TF-Pad24)") (class "Default")
      (node (ref "BM18") (pin "24") (pinfunction "TF_24") (pintype "passive+no_connect"))
    )
  )
)
